# lp_pic.net
KiCad netlist of a schematic drawn in EAGLE
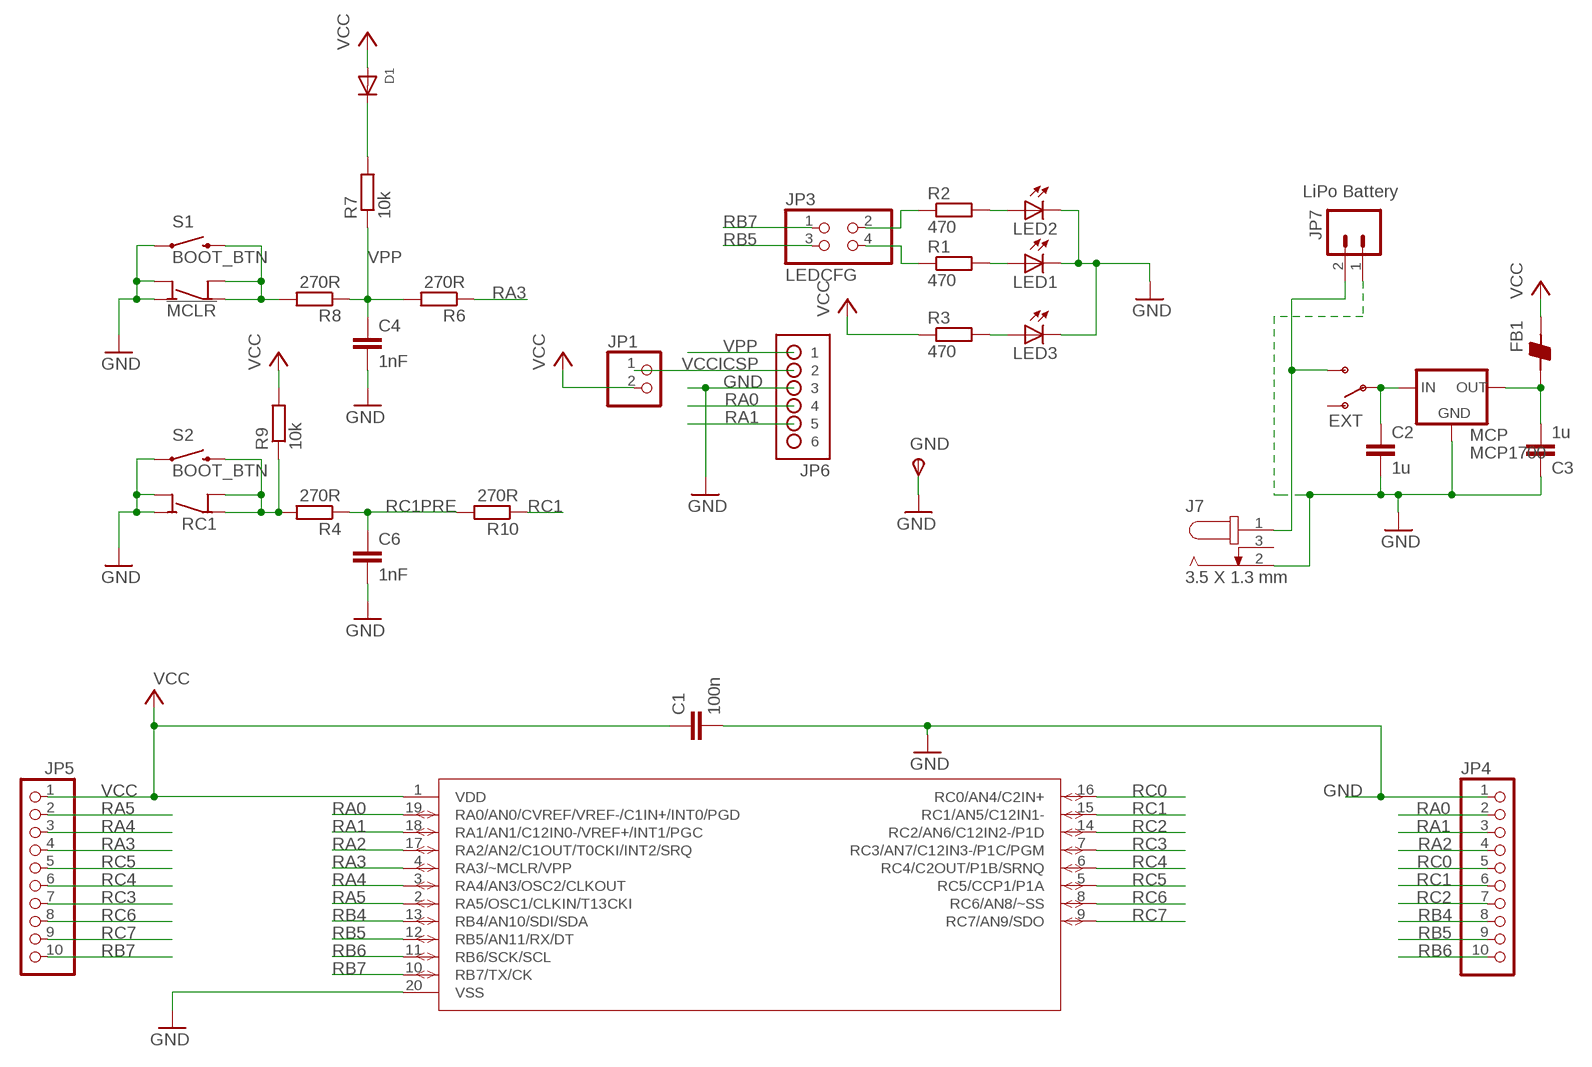
[diagram p0: schematic, sheet 1]

(export (version "E")
  (design (tool "Eeschema 10.0.6"))
  (components
    (comp (ref "!MCLR")
      (value "!MCLR")
      (footprint "eagle-import:6MMTACTILE_4PIN")
      (libsource (lib "eagle-import") (part "SPST4"))
    )
    (comp (ref "C1")
      (value "100n")
      (footprint "eagle-import:C0805")
      (libsource (lib "eagle-import") (part "C-EUC0805"))
    )
    (comp (ref "C2")
      (value "1u")
      (footprint "eagle-import:C0805")
      (libsource (lib "eagle-import") (part "C-EUC0805"))
    )
    (comp (ref "C3")
      (value "1u")
      (footprint "eagle-import:C0805")
      (libsource (lib "eagle-import") (part "C-EUC0805"))
    )
    (comp (ref "C4")
      (value "1nF")
      (footprint "eagle-import:C0805")
      (libsource (lib "eagle-import") (part "resistor_C-EUC0805"))
    )
    (comp (ref "C6")
      (value "1nF")
      (footprint "eagle-import:C0805")
      (libsource (lib "eagle-import") (part "resistor_C-EUC0805"))
    )
    (comp (ref "D1")
      (value "DIODESOD-323F")
      (footprint "eagle-import:SOD-323F")
      (libsource (lib "eagle-import") (part "DIODESOD-323F"))
    )
    (comp (ref "FB1")
      (value "BEAD-0805")
      (footprint "eagle-import:0805")
      (libsource (lib "eagle-import") (part "BEAD-0805"))
    )
    (comp (ref "GND")
      (value "TPSTP20R")
      (footprint "eagle-import:TP20R")
      (libsource (lib "eagle-import") (part "TPSTP20R"))
    )
    (comp (ref "J7")
      (value "3.5 X 1.3 mm")
      (footprint "eagle-import:3.5X1.3MM_DC_JACK")
      (libsource (lib "eagle-import") (part "DC_JACK_3.5X1.3MM"))
    )
    (comp (ref "JP1")
      (value "PINHD-1X2")
      (footprint "eagle-import:1X02")
      (libsource (lib "eagle-import") (part "PINHD-1X2"))
    )
    (comp (ref "JP3")
      (value "LEDCFG")
      (footprint "eagle-import:2X02")
      (libsource (lib "eagle-import") (part "PINHD-2X2"))
    )
    (comp (ref "JP4")
      (value "PH1X10OCT076")
      (footprint "eagle-import:PH1X10OCT76")
      (libsource (lib "eagle-import") (part "PH1X10OCT076"))
    )
    (comp (ref "JP5")
      (value "PH1X10OCT076")
      (footprint "eagle-import:PH1X10OCT76")
      (libsource (lib "eagle-import") (part "PH1X10OCT076"))
    )
    (comp (ref "JP6")
      (value "No Load")
      (footprint "eagle-import:HDR-1X6_OFFSET")
      (libsource (lib "eagle-import") (part "HDR-1X6-OFFSET"))
    )
    (comp (ref "JP7")
      (value "LiPo Battery")
      (footprint "eagle-import:JST-2-PTH")
      (libsource (lib "eagle-import") (part "M02JST-PTH-2"))
    )
    (comp (ref "LED1")
      (value "0")
      (footprint "eagle-import:CHIPLED_1206")
      (libsource (lib "eagle-import") (part "LEDCHIPLED_1206"))
    )
    (comp (ref "LED2")
      (value "0")
      (footprint "eagle-import:CHIPLED_1206")
      (libsource (lib "eagle-import") (part "LEDCHIPLED_1206"))
    )
    (comp (ref "LED3")
      (value "0")
      (footprint "eagle-import:CHIPLED_1206")
      (libsource (lib "eagle-import") (part "LEDCHIPLED_1206"))
    )
    (comp (ref "MCP")
      (value "MCP1700")
      (footprint "eagle-import:SOT-23")
      (libsource (lib "eagle-import") (part "MCP1700SOT-23"))
    )
    (comp (ref "ON")
      (value "EXT")
      (footprint "eagle-import:SWITCH-SPDT")
      (libsource (lib "eagle-import") (part "SWITCH-SPSTPTH"))
    )
    (comp (ref "R1")
      (value "470")
      (footprint "eagle-import:R0805")
      (libsource (lib "eagle-import") (part "R-EU_R0805"))
    )
    (comp (ref "R2")
      (value "470")
      (footprint "eagle-import:R0805")
      (libsource (lib "eagle-import") (part "R-EU_R0805"))
    )
    (comp (ref "R3")
      (value "470")
      (footprint "eagle-import:R0805")
      (libsource (lib "eagle-import") (part "R-EU_R0805"))
    )
    (comp (ref "R4")
      (value "270R")
      (footprint "eagle-import:R0805")
      (libsource (lib "eagle-import") (part "R-EU_R0805"))
    )
    (comp (ref "R6")
      (value "270R")
      (footprint "eagle-import:R0805")
      (libsource (lib "eagle-import") (part "R-EU_R0805"))
    )
    (comp (ref "R7")
      (value "10k")
      (footprint "eagle-import:R0805")
      (libsource (lib "eagle-import") (part "R-EU_R0805"))
    )
    (comp (ref "R8")
      (value "270R")
      (footprint "eagle-import:R0805")
      (libsource (lib "eagle-import") (part "R-EU_R0805"))
    )
    (comp (ref "R9")
      (value "10k")
      (footprint "eagle-import:R0805")
      (libsource (lib "eagle-import") (part "R-EU_R0805"))
    )
    (comp (ref "R10")
      (value "270R")
      (footprint "eagle-import:R0805")
      (libsource (lib "eagle-import") (part "R-EU_R0805"))
    )
    (comp (ref "RC1")
      (value "RC1")
      (footprint "eagle-import:6MMTACTILE_4PIN")
      (libsource (lib "eagle-import") (part "SPST4"))
    )
    (comp (ref "S1")
      (value "BOOT_BTN")
      (footprint "eagle-import:TACTILE-SWITCH-1101NE")
      (libsource (lib "eagle-import") (part "SWITCH-MOMENTARY-2-SMD-1101NE"))
    )
    (comp (ref "S2")
      (value "BOOT_BTN")
      (footprint "eagle-import:TACTILE-SWITCH-1101NE")
      (libsource (lib "eagle-import") (part "SWITCH-MOMENTARY-2-SMD-1101NE"))
    )
    (comp (ref "U$1")
      (value "PIC18F14K22-I/P")
      (footprint "eagle-import:DIP254P762X533-20")
      (fields (field (name "MPN") "PIC18F14k22-I/P"))
      (libsource (lib "eagle-import") (part "PIC18F14K22-I/P"))
    )
  )
  (nets
    (net (code "1") (name "/RA0") (class "Default")
      (node (ref "JP4") (pin "2") (pinfunction "2_2") (pintype "passive"))
      (node (ref "JP6") (pin "4") (pinfunction "4_4") (pintype "passive"))
      (node (ref "U$1") (pin "19") (pinfunction "RA0/AN0/CVREF/VREF-/C1IN+/INT0/PGD_19") (pintype "bidirectional"))
    )
    (net (code "2") (name "/RA1") (class "Default")
      (node (ref "JP4") (pin "3") (pinfunction "3_3") (pintype "passive"))
      (node (ref "JP6") (pin "5") (pinfunction "5_5") (pintype "passive"))
      (node (ref "U$1") (pin "18") (pinfunction "RA1/AN1/C12IN0-/VREF+/INT1/PGC_18") (pintype "bidirectional"))
    )
    (net (code "3") (name "/RA2") (class "Default")
      (node (ref "JP4") (pin "4") (pinfunction "4_4") (pintype "passive"))
      (node (ref "U$1") (pin "17") (pinfunction "RA2/AN2/C1OUT/T0CKI/INT2/SRQ_17") (pintype "bidirectional"))
    )
    (net (code "4") (name "/RA3") (class "Default")
      (node (ref "JP5") (pin "4") (pinfunction "4_4") (pintype "passive"))
      (node (ref "R6") (pin "1") (pinfunction "1_1") (pintype "passive"))
      (node (ref "U$1") (pin "4") (pinfunction "RA3/~{MCLR/VPP}_4") (pintype "bidirectional"))
    )
    (net (code "5") (name "/RA4") (class "Default")
      (node (ref "JP5") (pin "3") (pinfunction "3_3") (pintype "passive"))
      (node (ref "U$1") (pin "3") (pinfunction "RA4/AN3/OSC2/CLKOUT_3") (pintype "bidirectional"))
    )
    (net (code "6") (name "/RA5") (class "Default")
      (node (ref "JP5") (pin "2") (pinfunction "2_2") (pintype "passive"))
      (node (ref "U$1") (pin "2") (pinfunction "RA5/OSC1/CLKIN/T13CKI_2") (pintype "bidirectional"))
    )
    (net (code "7") (name "/RB4") (class "Default")
      (node (ref "JP4") (pin "8") (pinfunction "8_8") (pintype "passive"))
      (node (ref "U$1") (pin "13") (pinfunction "RB4/AN10/SDI/SDA_13") (pintype "bidirectional"))
    )
    (net (code "8") (name "/RB5") (class "Default")
      (node (ref "JP3") (pin "3") (pinfunction "3_3") (pintype "passive"))
      (node (ref "JP4") (pin "9") (pinfunction "9_9") (pintype "passive"))
      (node (ref "U$1") (pin "12") (pinfunction "RB5/AN11/RX/DT_12") (pintype "bidirectional"))
    )
    (net (code "9") (name "/RB6") (class "Default")
      (node (ref "JP4") (pin "10") (pinfunction "10_10") (pintype "passive"))
      (node (ref "U$1") (pin "11") (pinfunction "RB6/SCK/SCL_11") (pintype "bidirectional"))
    )
    (net (code "10") (name "/RB7") (class "Default")
      (node (ref "JP3") (pin "1") (pinfunction "1_1") (pintype "passive"))
      (node (ref "JP5") (pin "10") (pinfunction "10_10") (pintype "passive"))
      (node (ref "U$1") (pin "10") (pinfunction "RB7/TX/CK_10") (pintype "bidirectional"))
    )
    (net (code "11") (name "/RC0") (class "Default")
      (node (ref "JP4") (pin "5") (pinfunction "5_5") (pintype "passive"))
      (node (ref "U$1") (pin "16") (pinfunction "RC0/AN4/C2IN+_16") (pintype "bidirectional"))
    )
    (net (code "12") (name "/RC1") (class "Default")
      (node (ref "JP4") (pin "6") (pinfunction "6_6") (pintype "passive"))
      (node (ref "R10") (pin "1") (pinfunction "1_1") (pintype "passive"))
      (node (ref "U$1") (pin "15") (pinfunction "RC1/AN5/C12IN1-_15") (pintype "bidirectional"))
    )
    (net (code "13") (name "/RC1PRE") (class "Default")
      (node (ref "C6") (pin "1") (pinfunction "1_1") (pintype "passive"))
      (node (ref "R10") (pin "2") (pinfunction "2_2") (pintype "passive"))
      (node (ref "R4") (pin "1") (pinfunction "1_1") (pintype "passive"))
    )
    (net (code "14") (name "/RC2") (class "Default")
      (node (ref "JP4") (pin "7") (pinfunction "7_7") (pintype "passive"))
      (node (ref "U$1") (pin "14") (pinfunction "RC2/AN6/C12IN2-/P1D_14") (pintype "bidirectional"))
    )
    (net (code "15") (name "/RC3") (class "Default")
      (node (ref "JP5") (pin "7") (pinfunction "7_7") (pintype "passive"))
      (node (ref "U$1") (pin "7") (pinfunction "RC3/AN7/C12IN3-/P1C/PGM_7") (pintype "bidirectional"))
    )
    (net (code "16") (name "/RC4") (class "Default")
      (node (ref "JP5") (pin "6") (pinfunction "6_6") (pintype "passive"))
      (node (ref "U$1") (pin "6") (pinfunction "RC4/C2OUT/P1B/SRNQ_6") (pintype "bidirectional"))
    )
    (net (code "17") (name "/RC5") (class "Default")
      (node (ref "JP5") (pin "5") (pinfunction "5_5") (pintype "passive"))
      (node (ref "U$1") (pin "5") (pinfunction "RC5/CCP1/P1A_5") (pintype "bidirectional"))
    )
    (net (code "18") (name "/RC6") (class "Default")
      (node (ref "JP5") (pin "8") (pinfunction "8_8") (pintype "passive"))
      (node (ref "U$1") (pin "8") (pinfunction "RC6/AN8/~{SS}_8") (pintype "bidirectional"))
    )
    (net (code "19") (name "/RC7") (class "Default")
      (node (ref "JP5") (pin "9") (pinfunction "9_9") (pintype "passive"))
      (node (ref "U$1") (pin "9") (pinfunction "RC7/AN9/SDO_9") (pintype "bidirectional"))
    )
    (net (code "20") (name "/VCCICSP") (class "Default")
      (node (ref "JP1") (pin "1") (pinfunction "1_1") (pintype "passive"))
      (node (ref "JP6") (pin "2") (pinfunction "2_2") (pintype "passive"))
    )
    (net (code "21") (name "/VPP") (class "Default")
      (node (ref "C4") (pin "1") (pinfunction "1_1") (pintype "passive"))
      (node (ref "JP6") (pin "1") (pinfunction "1_1") (pintype "passive"))
      (node (ref "R6") (pin "2") (pinfunction "2_2") (pintype "passive"))
      (node (ref "R7") (pin "1") (pinfunction "1_1") (pintype "passive"))
      (node (ref "R8") (pin "1") (pinfunction "1_1") (pintype "passive"))
    )
    (net (code "22") (name "GND") (class "Default")
      (node (ref "!MCLR") (pin "A1") (pinfunction "NO_A1") (pintype "passive"))
      (node (ref "!MCLR") (pin "A2") (pinfunction "NO_A2") (pintype "passive"))
      (node (ref "C1") (pin "2") (pinfunction "2_2") (pintype "passive"))
      (node (ref "C2") (pin "2") (pinfunction "2_2") (pintype "passive"))
      (node (ref "C3") (pin "1") (pinfunction "1_1") (pintype "passive"))
      (node (ref "C4") (pin "2") (pinfunction "2_2") (pintype "passive"))
      (node (ref "C6") (pin "2") (pinfunction "2_2") (pintype "passive"))
      (node (ref "GND") (pin "TP") (pinfunction "PP_TP") (pintype "input"))
      (node (ref "J7") (pin "2") (pinfunction "2_2") (pintype "passive"))
      (node (ref "JP4") (pin "1") (pinfunction "1_1") (pintype "passive"))
      (node (ref "JP6") (pin "3") (pinfunction "3_3") (pintype "passive"))
      (node (ref "JP7") (pin "1") (pinfunction "1_1") (pintype "passive"))
      (node (ref "LED1") (pin "C") (pinfunction "C_C") (pintype "passive"))
      (node (ref "LED2") (pin "C") (pinfunction "C_C") (pintype "passive"))
      (node (ref "LED3") (pin "C") (pinfunction "C_C") (pintype "passive"))
      (node (ref "MCP") (pin "1") (pinfunction "GND_1") (pintype "input"))
      (node (ref "RC1") (pin "A1") (pinfunction "NO_A1") (pintype "passive"))
      (node (ref "RC1") (pin "A2") (pinfunction "NO_A2") (pintype "passive"))
      (node (ref "S1") (pin "1") (pinfunction "1_1") (pintype "passive"))
      (node (ref "S2") (pin "1") (pinfunction "1_1") (pintype "passive"))
      (node (ref "U$1") (pin "20") (pinfunction "VSS_20") (pintype "power_in"))
    )
    (net (code "23") (name "Net-(!MCLR-COM-PadB1)") (class "Default")
      (node (ref "!MCLR") (pin "B1") (pinfunction "COM_B1") (pintype "passive"))
      (node (ref "!MCLR") (pin "B2") (pinfunction "COM_B2") (pintype "passive"))
      (node (ref "R8") (pin "2") (pinfunction "2_2") (pintype "passive"))
      (node (ref "S1") (pin "2") (pinfunction "2_2") (pintype "passive"))
    )
    (net (code "24") (name "Net-(D1-PadC)") (class "Default")
      (node (ref "D1") (pin "C") (pinfunction "C_C") (pintype "passive"))
      (node (ref "R7") (pin "2") (pinfunction "2_2") (pintype "passive"))
    )
    (net (code "25") (name "Net-(FB1-P$1)") (class "Default")
      (node (ref "C3") (pin "2") (pinfunction "2_2") (pintype "passive"))
      (node (ref "FB1") (pin "1") (pinfunction "P$1_1") (pintype "passive"))
      (node (ref "MCP") (pin "2") (pinfunction "OUT_2") (pintype "passive"))
    )
    (net (code "26") (name "Net-(JP3-Pad2)") (class "Default")
      (node (ref "JP3") (pin "2") (pinfunction "2_2") (pintype "passive"))
      (node (ref "R2") (pin "1") (pinfunction "1_1") (pintype "passive"))
    )
    (net (code "27") (name "Net-(JP3-Pad4)") (class "Default")
      (node (ref "JP3") (pin "4") (pinfunction "4_4") (pintype "passive"))
      (node (ref "R1") (pin "1") (pinfunction "1_1") (pintype "passive"))
    )
    (net (code "28") (name "Net-(LED1-PadA)") (class "Default")
      (node (ref "LED1") (pin "A") (pinfunction "A_A") (pintype "passive"))
      (node (ref "R1") (pin "2") (pinfunction "2_2") (pintype "passive"))
    )
    (net (code "29") (name "Net-(LED2-PadA)") (class "Default")
      (node (ref "LED2") (pin "A") (pinfunction "A_A") (pintype "passive"))
      (node (ref "R2") (pin "2") (pinfunction "2_2") (pintype "passive"))
    )
    (net (code "30") (name "Net-(LED3-PadA)") (class "Default")
      (node (ref "LED3") (pin "A") (pinfunction "A_A") (pintype "passive"))
      (node (ref "R3") (pin "2") (pinfunction "2_2") (pintype "passive"))
    )
    (net (code "31") (name "Net-(MCP-IN)") (class "Default")
      (node (ref "C2") (pin "1") (pinfunction "1_1") (pintype "passive"))
      (node (ref "MCP") (pin "3") (pinfunction "IN_3") (pintype "input"))
      (node (ref "ON") (pin "2") (pinfunction "P_2") (pintype "passive"))
    )
    (net (code "32") (name "Net-(ON-S)") (class "Default")
      (node (ref "J7") (pin "1") (pinfunction "1_1") (pintype "passive"))
      (node (ref "JP7") (pin "2") (pinfunction "2_2") (pintype "passive"))
      (node (ref "ON") (pin "3") (pinfunction "S_3") (pintype "passive"))
    )
    (net (code "33") (name "Net-(R4-Pad2)") (class "Default")
      (node (ref "R4") (pin "2") (pinfunction "2_2") (pintype "passive"))
      (node (ref "R9") (pin "1") (pinfunction "1_1") (pintype "passive"))
      (node (ref "RC1") (pin "B1") (pinfunction "COM_B1") (pintype "passive"))
      (node (ref "RC1") (pin "B2") (pinfunction "COM_B2") (pintype "passive"))
      (node (ref "S2") (pin "2") (pinfunction "2_2") (pintype "passive"))
    )
    (net (code "34") (name "VCC") (class "Default")
      (node (ref "C1") (pin "1") (pinfunction "1_1") (pintype "passive"))
      (node (ref "D1") (pin "A") (pinfunction "A_A") (pintype "passive"))
      (node (ref "FB1") (pin "2") (pinfunction "P$2_2") (pintype "passive"))
      (node (ref "JP1") (pin "2") (pinfunction "2_2") (pintype "passive"))
      (node (ref "JP5") (pin "1") (pinfunction "1_1") (pintype "passive"))
      (node (ref "R3") (pin "1") (pinfunction "1_1") (pintype "passive"))
      (node (ref "R9") (pin "2") (pinfunction "2_2") (pintype "passive"))
      (node (ref "U$1") (pin "1") (pinfunction "VDD_1") (pintype "power_in"))
    )
    (net (code "35") (name "unconnected-(J7-Pad3)") (class "Default")
      (node (ref "J7") (pin "3") (pinfunction "3_3") (pintype "passive"))
    )
    (net (code "36") (name "unconnected-(JP6-Pad6)") (class "Default")
      (node (ref "JP6") (pin "6") (pinfunction "6_6") (pintype "passive"))
    )
    (net (code "37") (name "unconnected-(ON-O-Pad1)") (class "Default")
      (node (ref "ON") (pin "1") (pinfunction "O_1") (pintype "passive"))
    )
  )
)
